# FTDI_60X.net
KiCad netlist of a schematic drawn in Altium Designer
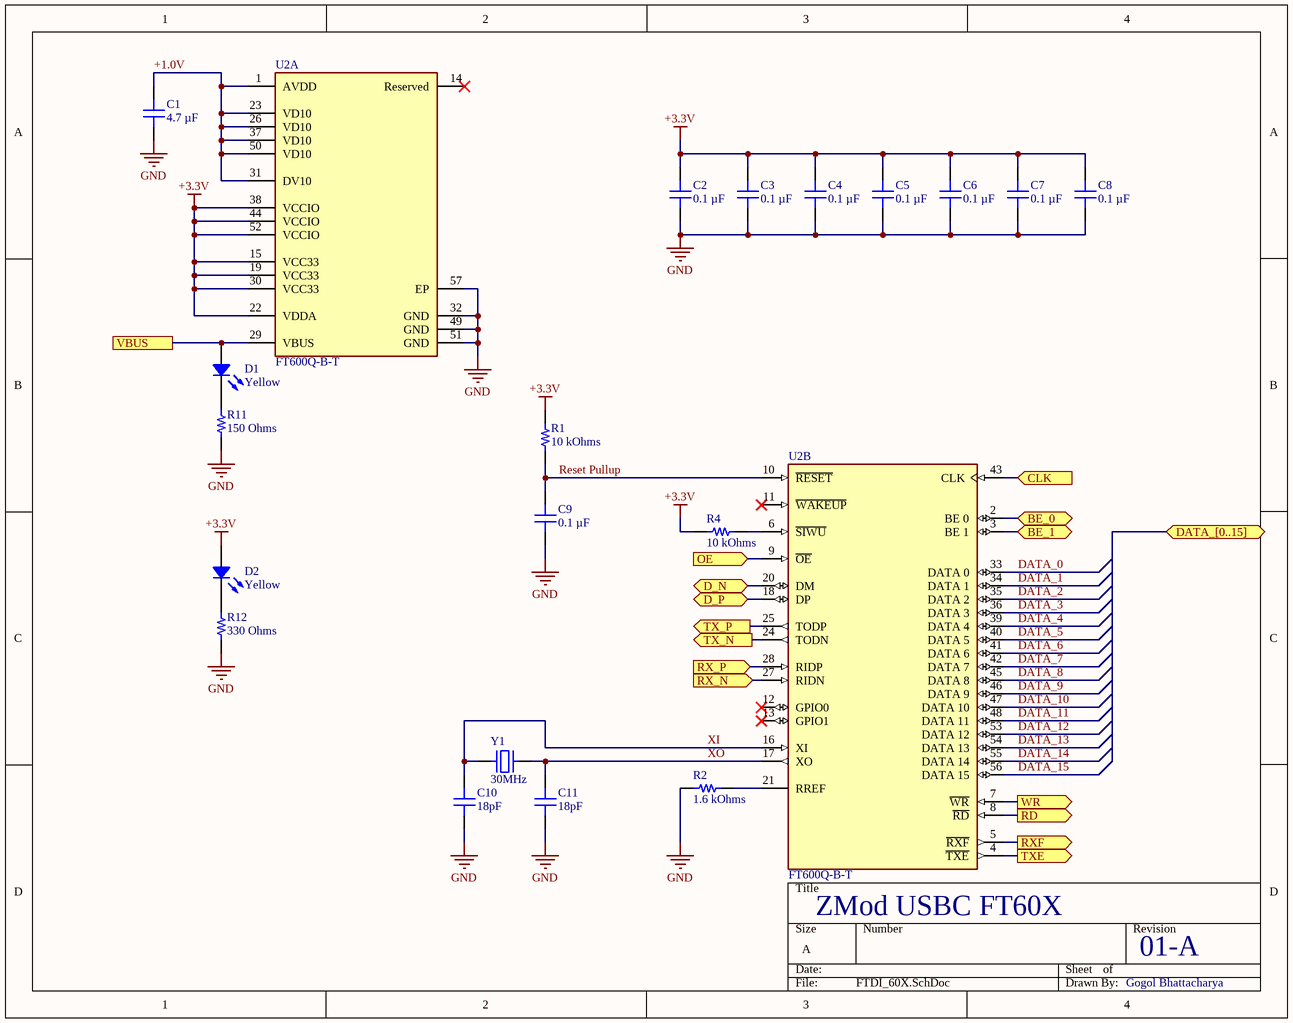
[diagram p0: FTDI_60X.SchDoc]

(export (version "E")
  (design (tool "Eeschema 10.0.6"))
  (components
    (comp (ref "C1")
      (value "4.7 µF")
      (footprint "CAPC1005X06N")
      (description "CAP CER 4.7UF 25V X5R 0603")
      (fields
        (field (name "PART NUMBER") "CL10A475KA8NQNC")
        (field (name "MANUFACTURER") "Samsung Electro-Mechanics")
      )
      (libsource (lib "Celestial Altium Library - altium_library") (part "Capacitor"))
    )
    (comp (ref "C2")
      (value "0.1 µF")
      (footprint "CAPC1005X06N")
      (description "CAP CER 0.1UF 50V X7R 0603")
      (fields (field (name "PART NUMBER") "C0603C104K5RAC7411") (field (name "MANUFACTURER") "KEMET"))
      (libsource (lib "Celestial Altium Library - altium_library") (part "Capacitor"))
    )
    (comp (ref "C3")
      (value "0.1 µF")
      (footprint "CAP 0603_1608")
      (description "CAP CER 0.1UF 50V X7R 0603")
      (fields (field (name "PART NUMBER") "C0603C104K5RAC7411") (field (name "MANUFACTURER") "KEMET"))
      (libsource (lib "Celestial Altium Library - altium_library") (part "Capacitor"))
    )
    (comp (ref "C4")
      (value "0.1 µF")
      (footprint "CAP 0603_1608")
      (description "CAP CER 0.1UF 50V X7R 0603")
      (fields (field (name "PART NUMBER") "C0603C104K5RAC7411") (field (name "MANUFACTURER") "KEMET"))
      (libsource (lib "Celestial Altium Library - altium_library") (part "Capacitor"))
    )
    (comp (ref "C5")
      (value "0.1 µF")
      (footprint "CAP 0603_1608")
      (description "CAP CER 0.1UF 50V X7R 0603")
      (fields (field (name "PART NUMBER") "C0603C104K5RAC7411") (field (name "MANUFACTURER") "KEMET"))
      (libsource (lib "Celestial Altium Library - altium_library") (part "Capacitor"))
    )
    (comp (ref "C6")
      (value "0.1 µF")
      (footprint "CAP 0603_1608")
      (description "CAP CER 0.1UF 50V X7R 0603")
      (fields (field (name "PART NUMBER") "C0603C104K5RAC7411") (field (name "MANUFACTURER") "KEMET"))
      (libsource (lib "Celestial Altium Library - altium_library") (part "Capacitor"))
    )
    (comp (ref "C7")
      (value "0.1 µF")
      (footprint "CAP 0603_1608")
      (description "CAP CER 0.1UF 50V X7R 0603")
      (fields (field (name "PART NUMBER") "C0603C104K5RAC7411") (field (name "MANUFACTURER") "KEMET"))
      (libsource (lib "Celestial Altium Library - altium_library") (part "Capacitor"))
    )
    (comp (ref "C8")
      (value "0.1 µF")
      (footprint "CAP 0603_1608")
      (description "CAP CER 0.1UF 50V X7R 0603")
      (fields (field (name "PART NUMBER") "C0603C104K5RAC7411") (field (name "MANUFACTURER") "KEMET"))
      (libsource (lib "Celestial Altium Library - altium_library") (part "Capacitor"))
    )
    (comp (ref "C9")
      (value "0.1 µF")
      (footprint "CAP 0603_1608")
      (description "CAP CER 0.1UF 50V X7R 0603")
      (fields (field (name "PART NUMBER") "C0603C104K5RAC7411") (field (name "MANUFACTURER") "KEMET"))
      (libsource (lib "Celestial Altium Library - altium_library") (part "Capacitor"))
    )
    (comp (ref "C10")
      (value "18pF")
      (footprint "CAP 0603_1608")
      (description "CAP CER 18PF 250V 0603")
      (fields (field (name "PART NUMBER") "SQCSVA180JAT1A") (field (name "MANUFACTURER") "AVX Corporation"))
      (libsource (lib "Celestial Altium Library - altium_library") (part "Capacitor"))
    )
    (comp (ref "C11")
      (value "18pF")
      (footprint "CAP 0603_1608")
      (description "CAP CER 18PF 250V 0603")
      (fields (field (name "PART NUMBER") "SQCSVA180JAT1A") (field (name "MANUFACTURER") "AVX Corporation"))
      (libsource (lib "Celestial Altium Library - altium_library") (part "Capacitor"))
    )
    (comp (ref "D1")
      (value "Yellow")
      (footprint "LED 1206_3216 YELLOW")
      (description "LED YELLOW CLEAR 1206 SMD")
      (fields
        (field (name "PART NUMBER") "CMD11-21VYC/TR8")
        (field (name "MANUFACTURER") "Visual Communications Company - VCC")
      )
      (libsource (lib "Celestial Altium Library - altium_library") (part "LED"))
    )
    (comp (ref "D2")
      (value "Yellow")
      (footprint "LED 1206_3216 YELLOW")
      (description "LED YELLOW CLEAR 1206 SMD")
      (fields
        (field (name "PART NUMBER") "CMD11-21VYC/TR8")
        (field (name "MANUFACTURER") "Visual Communications Company - VCC")
      )
      (libsource (lib "Celestial Altium Library - altium_library") (part "LED"))
    )
    (comp (ref "R1")
      (value "10 kOhms")
      (footprint "RESC1005X06N")
      (description "RES SMD 10K OHM 1% 1/10W 0603")
      (fields (field (name "PART NUMBER") "RT0603FRE0710KL") (field (name "MANUFACTURER") "Yageo"))
      (libsource (lib "Celestial Altium Library - altium_library") (part "Resistor"))
    )
    (comp (ref "R2")
      (value "1.6 kOhms")
      (footprint "RESC1005X06N")
      (description "RES SMD 1.6K OHM 1% 1/10W 0603")
      (fields (field (name "PART NUMBER") "CR0603-FX-1601ELF") (field (name "MANUFACTURER") "Bourns Inc."))
      (libsource (lib "Celestial Altium Library - altium_library") (part "Resistor"))
    )
    (comp (ref "R4")
      (value "10 kOhms")
      (footprint "RESC1005X06N")
      (description "RES SMD 10K OHM 1% 1/10W 0603")
      (fields (field (name "PART NUMBER") "RT0603FRE0710KL") (field (name "MANUFACTURER") "Yageo"))
      (libsource (lib "Celestial Altium Library - altium_library") (part "Resistor"))
    )
    (comp (ref "R11")
      (value "150 Ohms")
      (footprint "RES 0603_1608")
      (description "RES SMD 150 OHM 0.1% 1/8W 0603")
      (fields
        (field (name "PART NUMBER") "MCT0603MD1500BP100")
        (field (name "MANUFACTURER") "Vishay Beyschlag")
      )
      (libsource (lib "Celestial Altium Library - altium_library") (part "Resistor"))
    )
    (comp (ref "R12")
      (value "330 Ohms")
      (footprint "RES 0603_1608")
      (description "RESHIGHPOWERA 0603 330R 1% 1/4W")
      (fields (field (name "PART NUMBER") "CMP0603AFX-3300ELF") (field (name "MANUFACTURER") "Bourns Inc."))
      (libsource (lib "Celestial Altium Library - altium_library") (part "Resistor"))
    )
    (comp (ref "U2")
      (value "FT600Q-B-T")
      (footprint "FP-QFN-56-MFG")
      (description "USB Bus Controller, CMOS")
      (libsource (lib "Gogol Bhattacharya (Personal)") (part "514cddb991f3ba753bcacf4a91aa7af"))
    )
    (comp (ref "Y1")
      (value "30MHz")
      (footprint "ABRACON ABLS")
      (description "CRYSTAL 30.0000MHZ 18PF SMD")
      (fields
        (field (name "PART NUMBER") "ABLS-30.000MHZ-B4-F-T")
        (field (name "MANUFACTURER") "Abracon LLC")
      )
      (libsource (lib "Celestial Altium Library - altium_library") (part "Abracon Crystal ABLS"))
    )
  )
  (nets
    (net (code "1") (name "+3.3V") (class "Default")
      (node (ref "C2") (pin "2") (pinfunction "2_2") (pintype "passive"))
      (node (ref "C3") (pin "2") (pinfunction "2_2") (pintype "passive"))
      (node (ref "C4") (pin "2") (pinfunction "2_2") (pintype "passive"))
      (node (ref "C5") (pin "2") (pinfunction "2_2") (pintype "passive"))
      (node (ref "C6") (pin "2") (pinfunction "2_2") (pintype "passive"))
      (node (ref "C7") (pin "2") (pinfunction "2_2") (pintype "passive"))
      (node (ref "C8") (pin "2") (pinfunction "2_2") (pintype "passive"))
      (node (ref "D2") (pin "1") (pinfunction "1_1") (pintype "passive"))
      (node (ref "R1") (pin "2") (pinfunction "2_2") (pintype "passive"))
      (node (ref "R4") (pin "2") (pinfunction "2_2") (pintype "passive"))
      (node (ref "U2") (pin "15") (pinfunction "VCC33_15") (pintype "power_in"))
      (node (ref "U2") (pin "19") (pinfunction "VCC33_19") (pintype "power_in"))
      (node (ref "U2") (pin "22") (pinfunction "VDDA_22") (pintype "power_in"))
      (node (ref "U2") (pin "30") (pinfunction "VCC33_30") (pintype "power_in"))
      (node (ref "U2") (pin "38") (pinfunction "VCCIO_38") (pintype "power_in"))
      (node (ref "U2") (pin "44") (pinfunction "VCCIO_44") (pintype "power_in"))
      (node (ref "U2") (pin "52") (pinfunction "VCCIO_52") (pintype "power_in"))
    )
    (net (code "2") (name "/+1.0V") (class "Default")
      (node (ref "C1") (pin "2") (pinfunction "2_2") (pintype "passive"))
      (node (ref "U2") (pin "1") (pinfunction "AVDD_1") (pintype "power_in"))
      (node (ref "U2") (pin "23") (pinfunction "VD10_23") (pintype "power_in"))
      (node (ref "U2") (pin "26") (pinfunction "VD10_26") (pintype "power_in"))
      (node (ref "U2") (pin "31") (pinfunction "DV10_31") (pintype "power_in"))
      (node (ref "U2") (pin "37") (pinfunction "VD10_37") (pintype "power_in"))
      (node (ref "U2") (pin "50") (pinfunction "VD10_50") (pintype "power_in"))
    )
    (net (code "3") (name "/BE_0") (class "Default")
      (node (ref "U2") (pin "2") (pinfunction "BE_0_2") (pintype "bidirectional"))
    )
    (net (code "4") (name "/BE_1") (class "Default")
      (node (ref "U2") (pin "3") (pinfunction "BE_1_3") (pintype "bidirectional"))
    )
    (net (code "5") (name "/CLK") (class "Default")
      (node (ref "U2") (pin "43") (pinfunction "CLK_43") (pintype "input"))
    )
    (net (code "6") (name "/DATA_0") (class "Default")
      (node (ref "U2") (pin "33") (pinfunction "DATA_0_33") (pintype "bidirectional"))
    )
    (net (code "7") (name "/DATA_1") (class "Default")
      (node (ref "U2") (pin "34") (pinfunction "DATA_1_34") (pintype "bidirectional"))
    )
    (net (code "8") (name "/DATA_2") (class "Default")
      (node (ref "U2") (pin "35") (pinfunction "DATA_2_35") (pintype "bidirectional"))
    )
    (net (code "9") (name "/DATA_3") (class "Default")
      (node (ref "U2") (pin "36") (pinfunction "DATA_3_36") (pintype "bidirectional"))
    )
    (net (code "10") (name "/DATA_4") (class "Default")
      (node (ref "U2") (pin "39") (pinfunction "DATA_4_39") (pintype "bidirectional"))
    )
    (net (code "11") (name "/DATA_5") (class "Default")
      (node (ref "U2") (pin "40") (pinfunction "DATA_5_40") (pintype "bidirectional"))
    )
    (net (code "12") (name "/DATA_6") (class "Default")
      (node (ref "U2") (pin "41") (pinfunction "DATA_6_41") (pintype "bidirectional"))
    )
    (net (code "13") (name "/DATA_7") (class "Default")
      (node (ref "U2") (pin "42") (pinfunction "DATA_7_42") (pintype "bidirectional"))
    )
    (net (code "14") (name "/DATA_8") (class "Default")
      (node (ref "U2") (pin "45") (pinfunction "DATA_8_45") (pintype "bidirectional"))
    )
    (net (code "15") (name "/DATA_9") (class "Default")
      (node (ref "U2") (pin "46") (pinfunction "DATA_9_46") (pintype "bidirectional"))
    )
    (net (code "16") (name "/DATA_10") (class "Default")
      (node (ref "U2") (pin "47") (pinfunction "DATA_10_47") (pintype "bidirectional"))
    )
    (net (code "17") (name "/DATA_11") (class "Default")
      (node (ref "U2") (pin "48") (pinfunction "DATA_11_48") (pintype "bidirectional"))
    )
    (net (code "18") (name "/DATA_12") (class "Default")
      (node (ref "U2") (pin "53") (pinfunction "DATA_12_53") (pintype "bidirectional"))
    )
    (net (code "19") (name "/DATA_13") (class "Default")
      (node (ref "U2") (pin "54") (pinfunction "DATA_13_54") (pintype "bidirectional"))
    )
    (net (code "20") (name "/DATA_14") (class "Default")
      (node (ref "U2") (pin "55") (pinfunction "DATA_14_55") (pintype "bidirectional"))
    )
    (net (code "21") (name "/DATA_15") (class "Default")
      (node (ref "U2") (pin "56") (pinfunction "DATA_15_56") (pintype "bidirectional"))
    )
    (net (code "23") (name "/D_N") (class "Default")
      (node (ref "U2") (pin "20") (pinfunction "DM_20") (pintype "bidirectional"))
    )
    (net (code "24") (name "/D_P") (class "Default")
      (node (ref "U2") (pin "18") (pinfunction "DP_18") (pintype "bidirectional"))
    )
    (net (code "25") (name "/OE") (class "Default")
      (node (ref "U2") (pin "9") (pinfunction "~{OE}_9") (pintype "input"))
    )
    (net (code "26") (name "/RD") (class "Default")
      (node (ref "U2") (pin "8") (pinfunction "~{RD}_8") (pintype "input"))
    )
    (net (code "27") (name "/RXF") (class "Default")
      (node (ref "U2") (pin "5") (pinfunction "~{RXF}_5") (pintype "output"))
    )
    (net (code "28") (name "/RX_N") (class "Default")
      (node (ref "U2") (pin "27") (pinfunction "RIDN_27") (pintype "input"))
    )
    (net (code "29") (name "/RX_P") (class "Default")
      (node (ref "U2") (pin "28") (pinfunction "RIDP_28") (pintype "input"))
    )
    (net (code "30") (name "/Reset Pullup") (class "Default")
      (node (ref "C9") (pin "2") (pinfunction "2_2") (pintype "passive"))
      (node (ref "R1") (pin "1") (pinfunction "1_1") (pintype "passive"))
      (node (ref "U2") (pin "10") (pinfunction "~{RESET}_10") (pintype "input"))
    )
    (net (code "31") (name "/TXE") (class "Default")
      (node (ref "U2") (pin "4") (pinfunction "~{TXE}_4") (pintype "output"))
    )
    (net (code "32") (name "/TX_N") (class "Default")
      (node (ref "U2") (pin "24") (pinfunction "TODN_24") (pintype "output"))
    )
    (net (code "33") (name "/TX_P") (class "Default")
      (node (ref "U2") (pin "25") (pinfunction "TODP_25") (pintype "output"))
    )
    (net (code "34") (name "/VBUS") (class "Default")
      (node (ref "D1") (pin "1") (pinfunction "1_1") (pintype "passive"))
      (node (ref "U2") (pin "29") (pinfunction "VBUS_29") (pintype "power_in"))
    )
    (net (code "35") (name "/WR") (class "Default")
      (node (ref "U2") (pin "7") (pinfunction "~{WR}_7") (pintype "input"))
    )
    (net (code "36") (name "/XI") (class "Default")
      (node (ref "C10") (pin "2") (pinfunction "2_2") (pintype "passive"))
      (node (ref "U2") (pin "16") (pinfunction "XI_16") (pintype "input"))
      (node (ref "Y1") (pin "1") (pinfunction "1_1") (pintype "passive"))
    )
    (net (code "37") (name "/XO") (class "Default")
      (node (ref "C11") (pin "2") (pinfunction "2_2") (pintype "passive"))
      (node (ref "U2") (pin "17") (pinfunction "XO_17") (pintype "output"))
      (node (ref "Y1") (pin "2") (pinfunction "2_2") (pintype "passive"))
    )
    (net (code "38") (name "GND") (class "Default")
      (node (ref "C1") (pin "1") (pinfunction "1_1") (pintype "passive"))
      (node (ref "C10") (pin "1") (pinfunction "1_1") (pintype "passive"))
      (node (ref "C11") (pin "1") (pinfunction "1_1") (pintype "passive"))
      (node (ref "C2") (pin "1") (pinfunction "1_1") (pintype "passive"))
      (node (ref "C3") (pin "1") (pinfunction "1_1") (pintype "passive"))
      (node (ref "C4") (pin "1") (pinfunction "1_1") (pintype "passive"))
      (node (ref "C5") (pin "1") (pinfunction "1_1") (pintype "passive"))
      (node (ref "C6") (pin "1") (pinfunction "1_1") (pintype "passive"))
      (node (ref "C7") (pin "1") (pinfunction "1_1") (pintype "passive"))
      (node (ref "C8") (pin "1") (pinfunction "1_1") (pintype "passive"))
      (node (ref "C9") (pin "1") (pinfunction "1_1") (pintype "passive"))
      (node (ref "R11") (pin "1") (pinfunction "1_1") (pintype "passive"))
      (node (ref "R12") (pin "1") (pinfunction "1_1") (pintype "passive"))
      (node (ref "R2") (pin "1") (pinfunction "1_1") (pintype "passive"))
      (node (ref "U2") (pin "32") (pinfunction "GND_32") (pintype "power_in"))
      (node (ref "U2") (pin "49") (pinfunction "GND_49") (pintype "power_in"))
      (node (ref "U2") (pin "51") (pinfunction "GND_51") (pintype "power_in"))
      (node (ref "U2") (pin "57") (pinfunction "EP_57") (pintype "power_in"))
    )
    (net (code "39") (name "Net-(D1-Pad2)") (class "Default")
      (node (ref "D1") (pin "2") (pinfunction "2_2") (pintype "passive"))
      (node (ref "R11") (pin "2") (pinfunction "2_2") (pintype "passive"))
    )
    (net (code "40") (name "Net-(D2-Pad2)") (class "Default")
      (node (ref "D2") (pin "2") (pinfunction "2_2") (pintype "passive"))
      (node (ref "R12") (pin "2") (pinfunction "2_2") (pintype "passive"))
    )
    (net (code "41") (name "Net-(U2B-RREF)") (class "Default")
      (node (ref "R2") (pin "2") (pinfunction "2_2") (pintype "passive"))
      (node (ref "U2") (pin "21") (pinfunction "RREF_21") (pintype "passive"))
    )
    (net (code "42") (name "Net-(U2B-~{SIWU})") (class "Default")
      (node (ref "R4") (pin "1") (pinfunction "1_1") (pintype "passive"))
      (node (ref "U2") (pin "6") (pinfunction "~{SIWU}_6") (pintype "input"))
    )
    (net (code "43") (name "unconnected-(U2A-Reserved-Pad14)") (class "Default")
      (node (ref "U2") (pin "14") (pinfunction "Reserved_14") (pintype "passive+no_connect"))
    )
    (net (code "44") (name "unconnected-(U2B-GPIO0-Pad12)") (class "Default")
      (node (ref "U2") (pin "12") (pinfunction "GPIO0_12") (pintype "bidirectional+no_connect"))
    )
    (net (code "45") (name "unconnected-(U2B-GPIO1-Pad13)") (class "Default")
      (node (ref "U2") (pin "13") (pinfunction "GPIO1_13") (pintype "bidirectional+no_connect"))
    )
    (net (code "46") (name "unconnected-(U2B-~{WAKEUP}-Pad11)") (class "Default")
      (node (ref "U2") (pin "11") (pinfunction "~{WAKEUP}_11") (pintype "input+no_connect"))
    )
  )
)
